# Attachments.net
KiCad netlist of a schematic drawn in Altium Designer
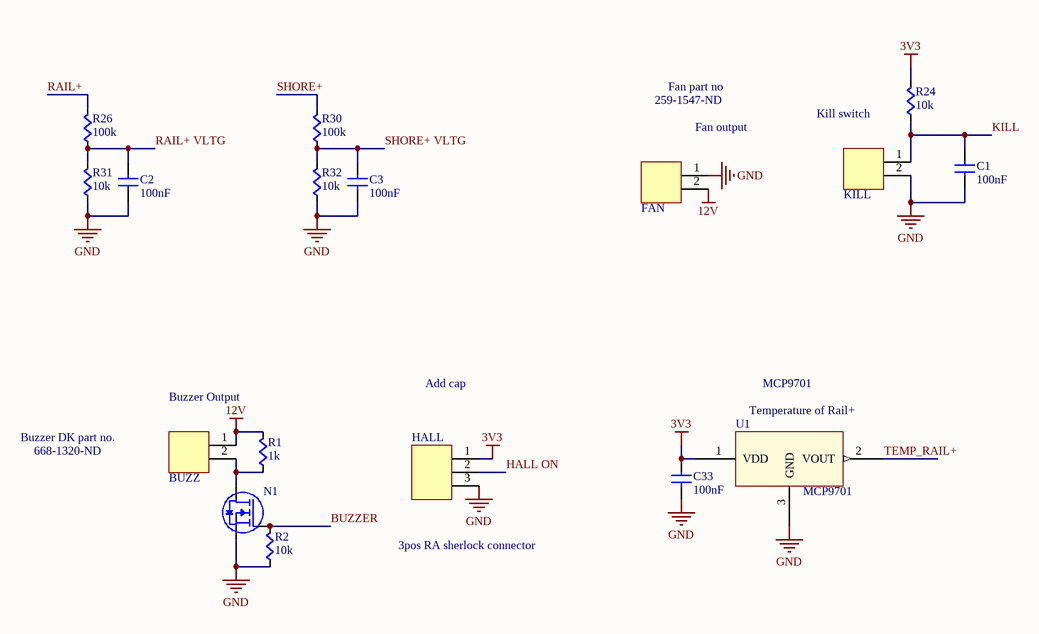
[diagram p0: Attachments.SchDoc]

(export (version "E")
  (design (tool "Eeschema 10.0.6"))
  (components
    (comp (ref "BUZZ")
      (value "2-pin Horz Sherlock")
      (footprint "MOLEX-HDR-1X2-SHERLOCK-HORZ")
      (fields
        (field (name "MANUFACTURER PART NUMBER") "0353630260")
        (field (name "MANUFACTURER") "Molex Inc")
      )
      (libsource (lib "SubjuGator8") (part "MOLEX-HDR-1x2-SHERLOCK_RA"))
    )
    (comp (ref "C1")
      (value "100nF")
      (footprint "CAPC0603")
      (fields (field (name "Comment") "Cap"))
      (libsource (lib "SubjuGator8") (part "Cap"))
    )
    (comp (ref "C2")
      (value "100nF")
      (footprint "CAPC0603")
      (fields (field (name "Comment") "Cap"))
      (libsource (lib "SubjuGator8") (part "Cap"))
    )
    (comp (ref "C3")
      (value "100nF")
      (footprint "CAPC0603")
      (fields (field (name "Comment") "Cap"))
      (libsource (lib "SubjuGator8") (part "Cap"))
    )
    (comp (ref "C33")
      (value "100nF")
      (footprint "CAPC0603")
      (fields (field (name "Comment") "Cap"))
      (libsource (lib "SubjuGator8") (part "Cap"))
    )
    (comp (ref "FAN")
      (value "2-pin Horz Sherlock")
      (footprint "MOLEX-HDR-1X2-SHERLOCK-HORZ")
      (fields
        (field (name "MANUFACTURER PART NUMBER") "0353630260")
        (field (name "MANUFACTURER") "Molex Inc")
      )
      (libsource (lib "SubjuGator8") (part "MOLEX-HDR-1x2-SHERLOCK_RA"))
    )
    (comp (ref "HALL")
      (value "3pos RA sherlock connector")
      (footprint "MOLEX-HDR-1X3-SHERLOCK-RA")
      (description "Header, Molex, 2mm Pitch Sherlock Header, Single Row, Right Angle 3 Circuits, Length 3.3mm")
      (fields
        (field (name "MANUFACTURER PART NUMBER") "35363-0360")
        (field (name "MANUFACTURER") "Molex Connector Corporation")
      )
      (libsource (lib "SubjuGator8") (part "MOLEX-HDR-1x3-SHERLOCK_RA"))
    )
    (comp (ref "KILL")
      (value "2-pin Horz Sherlock")
      (footprint "MOLEX-HDR-1X2-SHERLOCK-HORZ")
      (fields
        (field (name "MANUFACTURER PART NUMBER") "0353630260")
        (field (name "MANUFACTURER") "Molex Inc")
      )
      (libsource (lib "SubjuGator8") (part "MOLEX-HDR-1x2-SHERLOCK_RA"))
    )
    (comp (ref "N1")
      (value "NMOSFET")
      (footprint "2N7002P,215")
      (description "NMOSFET Template")
      (libsource (lib "SubjuGator8") (part "NMOSFET"))
    )
    (comp (ref "R1")
      (value "1k")
      (footprint "RES0603")
      (fields (field (name "Comment") "Res"))
      (libsource (lib "SubjuGator8") (part "Res"))
    )
    (comp (ref "R2")
      (value "10k")
      (footprint "RES0603")
      (fields (field (name "Comment") "Res"))
      (libsource (lib "SubjuGator8") (part "Res"))
    )
    (comp (ref "R24")
      (value "10k")
      (footprint "RES0603")
      (fields (field (name "Comment") "Res"))
      (libsource (lib "SubjuGator8") (part "Res"))
    )
    (comp (ref "R26")
      (value "100k")
      (footprint "RES0603")
      (fields (field (name "Comment") "Res"))
      (libsource (lib "SubjuGator8") (part "Res"))
    )
    (comp (ref "R30")
      (value "100k")
      (footprint "RES0603")
      (fields (field (name "Comment") "Res"))
      (libsource (lib "SubjuGator8") (part "Res"))
    )
    (comp (ref "R31")
      (value "10k")
      (footprint "RES0603")
      (fields (field (name "Comment") "Res"))
      (libsource (lib "SubjuGator8") (part "Res"))
    )
    (comp (ref "R32")
      (value "10k")
      (footprint "RES0603")
      (fields (field (name "Comment") "Res"))
      (libsource (lib "SubjuGator8") (part "Res"))
    )
    (comp (ref "U1")
      (value "MCP9701")
      (footprint "MCP970X-E/TT")
      (description "Low-Power Linear Active Thermistor ICs")
      (libsource (lib "SubjuGator8") (part "MCP970x"))
    )
  )
  (nets
    (net (code "1") (name "/BUZZER") (class "Default")
      (node (ref "N1") (pin "1") (pinfunction "G_1") (pintype "passive"))
      (node (ref "R2") (pin "1") (pinfunction "A_1") (pintype "passive"))
    )
    (net (code "2") (name "/HALL ON") (class "Default")
      (node (ref "HALL") (pin "2") (pinfunction "2_2") (pintype "passive"))
    )
    (net (code "3") (name "/KILL") (class "Default")
      (node (ref "C1") (pin "1") (pinfunction "A_1") (pintype "passive"))
      (node (ref "KILL") (pin "1") (pinfunction "1_1") (pintype "passive"))
      (node (ref "R24") (pin "2") (pinfunction "B_2") (pintype "passive"))
    )
    (net (code "4") (name "/RAIL+") (class "Default")
      (node (ref "R26") (pin "1") (pinfunction "A_1") (pintype "passive"))
    )
    (net (code "5") (name "/RAIL+ VLTG") (class "Default")
      (node (ref "C2") (pin "1") (pinfunction "A_1") (pintype "passive"))
      (node (ref "R26") (pin "2") (pinfunction "B_2") (pintype "passive"))
      (node (ref "R31") (pin "1") (pinfunction "A_1") (pintype "passive"))
    )
    (net (code "6") (name "/SHORE+") (class "Default")
      (node (ref "R30") (pin "1") (pinfunction "A_1") (pintype "passive"))
    )
    (net (code "7") (name "/SHORE+ VLTG") (class "Default")
      (node (ref "C3") (pin "1") (pinfunction "A_1") (pintype "passive"))
      (node (ref "R30") (pin "2") (pinfunction "B_2") (pintype "passive"))
      (node (ref "R32") (pin "1") (pinfunction "A_1") (pintype "passive"))
    )
    (net (code "8") (name "/TEMP_RAIL+") (class "Default")
      (node (ref "U1") (pin "2") (pinfunction "VOUT_2") (pintype "output"))
    )
    (net (code "9") (name "3V3") (class "Default")
      (node (ref "C33") (pin "2") (pinfunction "B_2") (pintype "passive"))
      (node (ref "HALL") (pin "1") (pinfunction "1_1") (pintype "passive"))
      (node (ref "R24") (pin "1") (pinfunction "A_1") (pintype "passive"))
      (node (ref "U1") (pin "1") (pinfunction "VDD_1") (pintype "power_in"))
    )
    (net (code "10") (name "12V") (class "Default")
      (node (ref "BUZZ") (pin "1") (pinfunction "1_1") (pintype "passive"))
      (node (ref "FAN") (pin "2") (pinfunction "2_2") (pintype "passive"))
      (node (ref "R1") (pin "1") (pinfunction "A_1") (pintype "passive"))
    )
    (net (code "11") (name "GND") (class "Default")
      (node (ref "C1") (pin "2") (pinfunction "B_2") (pintype "passive"))
      (node (ref "C2") (pin "2") (pinfunction "B_2") (pintype "passive"))
      (node (ref "C3") (pin "2") (pinfunction "B_2") (pintype "passive"))
      (node (ref "C33") (pin "1") (pinfunction "A_1") (pintype "passive"))
      (node (ref "FAN") (pin "1") (pinfunction "1_1") (pintype "passive"))
      (node (ref "HALL") (pin "3") (pinfunction "3_3") (pintype "passive"))
      (node (ref "KILL") (pin "2") (pinfunction "2_2") (pintype "passive"))
      (node (ref "N1") (pin "2") (pinfunction "S_2") (pintype "passive"))
      (node (ref "R2") (pin "2") (pinfunction "B_2") (pintype "passive"))
      (node (ref "R31") (pin "2") (pinfunction "B_2") (pintype "passive"))
      (node (ref "R32") (pin "2") (pinfunction "B_2") (pintype "passive"))
      (node (ref "U1") (pin "3") (pinfunction "GND_3") (pintype "power_in"))
    )
    (net (code "12") (name "Net-(N1-D)") (class "Default")
      (node (ref "BUZZ") (pin "2") (pinfunction "2_2") (pintype "passive"))
      (node (ref "N1") (pin "3") (pinfunction "D_3") (pintype "passive"))
      (node (ref "R1") (pin "2") (pinfunction "B_2") (pintype "passive"))
    )
  )
)
